# design.net
KiCad netlist of a schematic drawn in Altium Designer
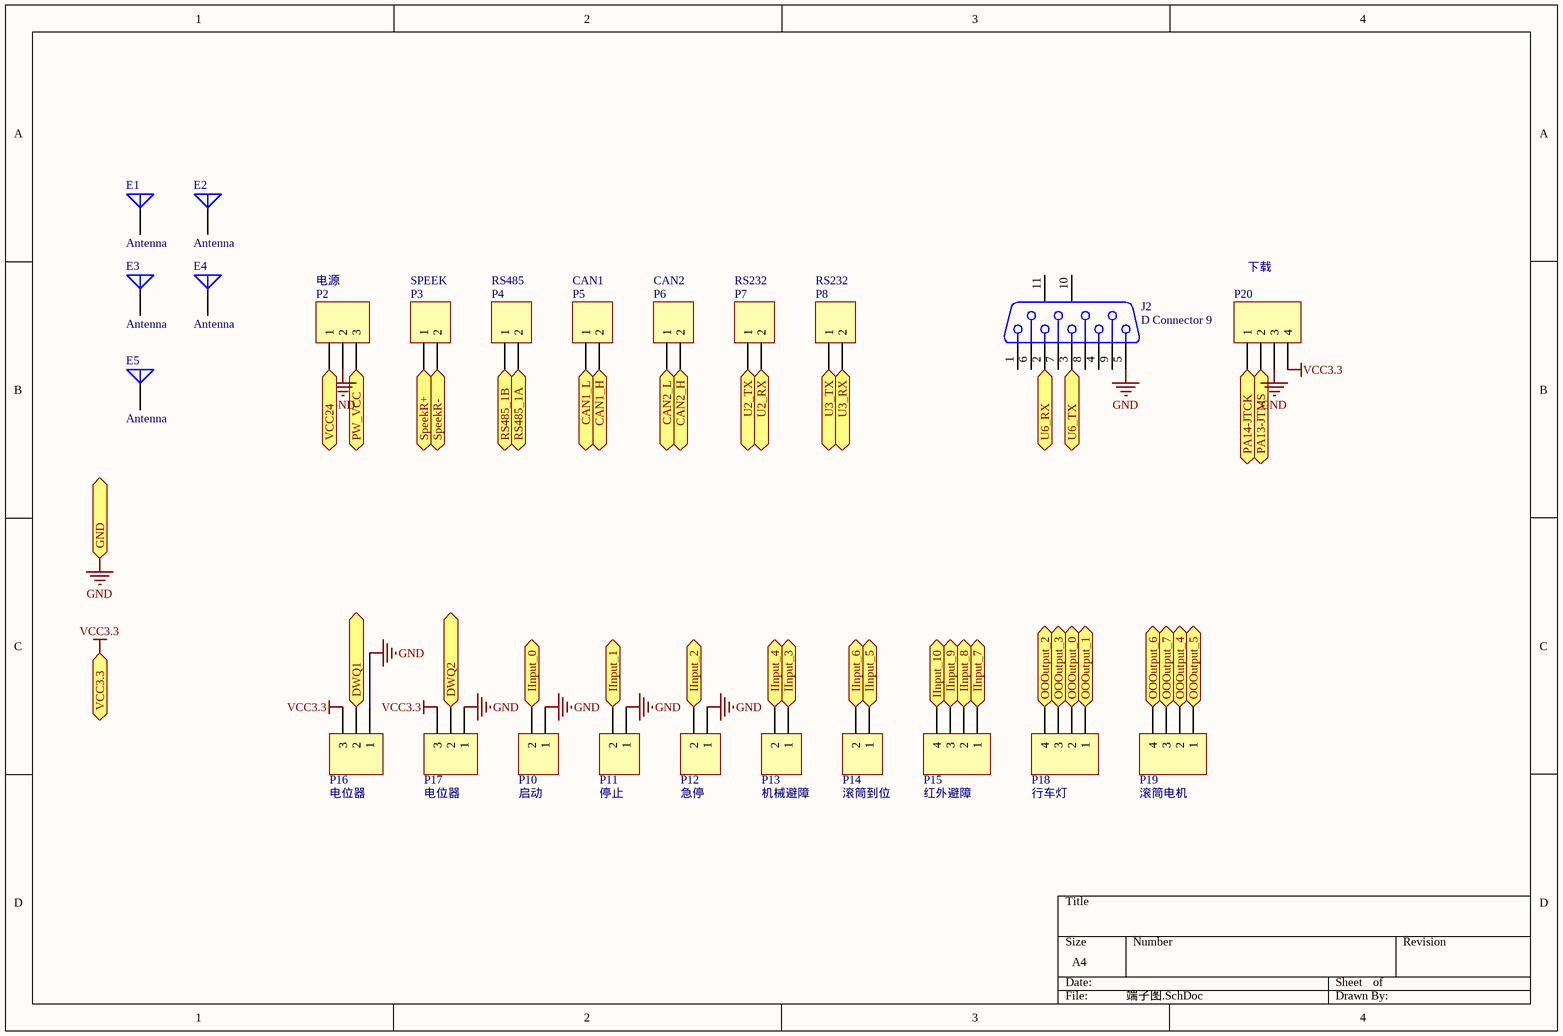
[diagram p0: 端子图.SchDoc]

(export (version "E")
  (design (tool "Eeschema 10.0.6"))
  (components
    (comp (ref "E1")
      (value "Antenna")
      (footprint "定位孔 Φ3.2")
      (description "Generic Antenna")
      (fields (field (name "PUBLISHER") "Altium Limited"))
      (libsource (lib "Miscellaneous Devices") (part "Antenna"))
    )
    (comp (ref "E2")
      (value "Antenna")
      (footprint "定位孔 Φ3.2")
      (description "Generic Antenna")
      (fields (field (name "PUBLISHER") "Altium Limited"))
      (libsource (lib "Miscellaneous Devices") (part "Antenna"))
    )
    (comp (ref "E3")
      (value "Antenna")
      (footprint "定位孔 Φ3.2")
      (description "Generic Antenna")
      (fields (field (name "PUBLISHER") "Altium Limited"))
      (libsource (lib "Miscellaneous Devices") (part "Antenna"))
    )
    (comp (ref "E4")
      (value "Antenna")
      (footprint "定位孔 Φ3.2")
      (description "Generic Antenna")
      (fields (field (name "PUBLISHER") "Altium Limited"))
      (libsource (lib "Miscellaneous Devices") (part "Antenna"))
    )
    (comp (ref "E5")
      (value "Antenna")
      (footprint "定位孔 Φ3.2")
      (description "Generic Antenna")
      (fields (field (name "PUBLISHER") "Altium Limited"))
      (libsource (lib "Miscellaneous Devices") (part "Antenna"))
    )
    (comp (ref "J2")
      (value "D Connector 9")
      (footprint "DSUB1.385-2H9")
      (description "Receptacle Assembly, 9 Position, Right Angle")
      (fields (field (name "PUBLISHER") "Altium Limited"))
      (libsource (lib "Miscellaneous Connectors") (part "D Connector 9"))
    )
    (comp (ref "P2")
      (value "电源")
      (footprint "DZ-3-5.08")
      (description "Header, 3-Pin")
      (fields (field (name "PUBLISHER") "Altium Limited"))
      (libsource (lib "") (part "Header 3_1"))
    )
    (comp (ref "P3")
      (value "SPEEK")
      (footprint "DZ-2-5.08")
      (description "Header, 2-Pin")
      (fields (field (name "PUBLISHER") "Altium Limited"))
      (libsource (lib "") (part "Header 2_1"))
    )
    (comp (ref "P4")
      (value "RS485")
      (footprint "DZ-2-5.08")
      (description "Header, 2-Pin")
      (fields (field (name "PUBLISHER") "Altium Limited"))
      (libsource (lib "") (part "Header 2_1"))
    )
    (comp (ref "P5")
      (value "CAN1")
      (footprint "DZ-2-5.08")
      (description "Header, 2-Pin")
      (fields (field (name "PUBLISHER") "Altium Limited"))
      (libsource (lib "") (part "Header 2_1"))
    )
    (comp (ref "P6")
      (value "CAN2")
      (footprint "DZ-2-5.08")
      (description "Header, 2-Pin")
      (fields (field (name "PUBLISHER") "Altium Limited"))
      (libsource (lib "") (part "Header 2_1"))
    )
    (comp (ref "P7")
      (value "RS232")
      (footprint "DZ-2-5.08")
      (description "Header, 2-Pin")
      (fields (field (name "PUBLISHER") "Altium Limited"))
      (libsource (lib "") (part "Header 2_1"))
    )
    (comp (ref "P8")
      (value "RS232")
      (footprint "DZ-2-5.08")
      (description "Header, 2-Pin")
      (fields (field (name "PUBLISHER") "Altium Limited"))
      (libsource (lib "") (part "Header 2_1"))
    )
    (comp (ref "P10")
      (value "启动")
      (footprint "DZ-2-5.08")
      (description "Header, 2-Pin")
      (fields (field (name "PUBLISHER") "Altium Limited"))
      (libsource (lib "Miscellaneous Connectors") (part "Header 2"))
    )
    (comp (ref "P11")
      (value "停止")
      (footprint "DZ-2-5.08")
      (description "Header, 2-Pin")
      (fields (field (name "PUBLISHER") "Altium Limited"))
      (libsource (lib "Miscellaneous Connectors") (part "Header 2"))
    )
    (comp (ref "P12")
      (value "急停")
      (footprint "DZ-2-5.08")
      (description "Header, 2-Pin")
      (fields (field (name "PUBLISHER") "Altium Limited"))
      (libsource (lib "Miscellaneous Connectors") (part "Header 2"))
    )
    (comp (ref "P13")
      (value "机械避障")
      (footprint "DZ-2-5.08")
      (description "Header, 2-Pin")
      (fields (field (name "PUBLISHER") "Altium Limited"))
      (libsource (lib "Miscellaneous Connectors") (part "Header 2"))
    )
    (comp (ref "P14")
      (value "滚筒到位")
      (footprint "DZ-2-5.08")
      (description "Header, 2-Pin")
      (fields (field (name "PUBLISHER") "Altium Limited"))
      (libsource (lib "Miscellaneous Connectors") (part "Header 2"))
    )
    (comp (ref "P15")
      (value "红外避障")
      (footprint "DZ-4-5.08")
      (description "Header, 4-Pin")
      (fields (field (name "PUBLISHER") "Altium Limited"))
      (libsource (lib "Miscellaneous Connectors") (part "Header 4"))
    )
    (comp (ref "P16")
      (value "电位器")
      (footprint "DZ-3-5.08")
      (description "Header, 3-Pin")
      (fields (field (name "PUBLISHER") "Altium Limited"))
      (libsource (lib "Miscellaneous Connectors") (part "Header 3"))
    )
    (comp (ref "P17")
      (value "电位器")
      (footprint "DZ-3-5.08")
      (description "Header, 3-Pin")
      (fields (field (name "PUBLISHER") "Altium Limited"))
      (libsource (lib "Miscellaneous Connectors") (part "Header 3"))
    )
    (comp (ref "P18")
      (value "行车灯")
      (footprint "DZ-4-5.08")
      (description "Header, 4-Pin")
      (fields (field (name "PUBLISHER") "Altium Limited"))
      (libsource (lib "Miscellaneous Connectors") (part "Header 4"))
    )
    (comp (ref "P19")
      (value "滚筒电机")
      (footprint "DZ-4-5.08")
      (description "Header, 4-Pin")
      (fields (field (name "PUBLISHER") "Altium Limited"))
      (libsource (lib "Miscellaneous Connectors") (part "Header 4"))
    )
    (comp (ref "P20")
      (value "下载")
      (footprint "DZ-4-5.08")
      (description "Header, 4-Pin")
      (fields (field (name "PUBLISHER") "Altium Limited"))
      (libsource (lib "") (part "Header 4_1"))
    )
  )
  (nets
    (net (code "1") (name "/CAN1_H") (class "Default")
      (node (ref "P5") (pin "2") (pinfunction "2_2") (pintype "passive"))
    )
    (net (code "2") (name "/CAN1_L") (class "Default")
      (node (ref "P5") (pin "1") (pinfunction "1_1") (pintype "passive"))
    )
    (net (code "3") (name "/CAN2_H") (class "Default")
      (node (ref "P6") (pin "2") (pinfunction "2_2") (pintype "passive"))
    )
    (net (code "4") (name "/CAN2_L") (class "Default")
      (node (ref "P6") (pin "1") (pinfunction "1_1") (pintype "passive"))
    )
    (net (code "5") (name "/DWQ1") (class "Default")
      (node (ref "P16") (pin "2") (pinfunction "2_2") (pintype "passive"))
    )
    (net (code "6") (name "/DWQ2") (class "Default")
      (node (ref "P17") (pin "2") (pinfunction "2_2") (pintype "passive"))
    )
    (net (code "7") (name "/IInput_0") (class "Default")
      (node (ref "P10") (pin "2") (pinfunction "2_2") (pintype "passive"))
    )
    (net (code "8") (name "/IInput_1") (class "Default")
      (node (ref "P11") (pin "2") (pinfunction "2_2") (pintype "passive"))
    )
    (net (code "9") (name "/IInput_2") (class "Default")
      (node (ref "P12") (pin "2") (pinfunction "2_2") (pintype "passive"))
    )
    (net (code "10") (name "/IInput_3") (class "Default")
      (node (ref "P13") (pin "1") (pinfunction "1_1") (pintype "passive"))
    )
    (net (code "11") (name "/IInput_4") (class "Default")
      (node (ref "P13") (pin "2") (pinfunction "2_2") (pintype "passive"))
    )
    (net (code "12") (name "/IInput_5") (class "Default")
      (node (ref "P14") (pin "1") (pinfunction "1_1") (pintype "passive"))
    )
    (net (code "13") (name "/IInput_6") (class "Default")
      (node (ref "P14") (pin "2") (pinfunction "2_2") (pintype "passive"))
    )
    (net (code "14") (name "/IInput_7") (class "Default")
      (node (ref "P15") (pin "1") (pinfunction "1_1") (pintype "passive"))
    )
    (net (code "15") (name "/IInput_8") (class "Default")
      (node (ref "P15") (pin "2") (pinfunction "2_2") (pintype "passive"))
    )
    (net (code "16") (name "/IInput_9") (class "Default")
      (node (ref "P15") (pin "3") (pinfunction "3_3") (pintype "passive"))
    )
    (net (code "17") (name "/IInput_10") (class "Default")
      (node (ref "P15") (pin "4") (pinfunction "4_4") (pintype "passive"))
    )
    (net (code "18") (name "/OOOutput_0") (class "Default")
      (node (ref "P18") (pin "2") (pinfunction "2_2") (pintype "passive"))
    )
    (net (code "19") (name "/OOOutput_1") (class "Default")
      (node (ref "P18") (pin "1") (pinfunction "1_1") (pintype "passive"))
    )
    (net (code "20") (name "/OOOutput_2") (class "Default")
      (node (ref "P18") (pin "4") (pinfunction "4_4") (pintype "passive"))
    )
    (net (code "21") (name "/OOOutput_3") (class "Default")
      (node (ref "P18") (pin "3") (pinfunction "3_3") (pintype "passive"))
    )
    (net (code "22") (name "/OOOutput_4") (class "Default")
      (node (ref "P19") (pin "2") (pinfunction "2_2") (pintype "passive"))
    )
    (net (code "23") (name "/OOOutput_5") (class "Default")
      (node (ref "P19") (pin "1") (pinfunction "1_1") (pintype "passive"))
    )
    (net (code "24") (name "/OOOutput_6") (class "Default")
      (node (ref "P19") (pin "4") (pinfunction "4_4") (pintype "passive"))
    )
    (net (code "25") (name "/OOOutput_7") (class "Default")
      (node (ref "P19") (pin "3") (pinfunction "3_3") (pintype "passive"))
    )
    (net (code "26") (name "/PA13-JTMS") (class "Default")
      (node (ref "P20") (pin "2") (pinfunction "2_2") (pintype "passive"))
    )
    (net (code "27") (name "/PA14-JTCK") (class "Default")
      (node (ref "P20") (pin "1") (pinfunction "1_1") (pintype "passive"))
    )
    (net (code "28") (name "/PW_VCC") (class "Default")
      (node (ref "P2") (pin "3") (pinfunction "3_3") (pintype "passive"))
    )
    (net (code "29") (name "/RS485_1A") (class "Default")
      (node (ref "P4") (pin "2") (pinfunction "2_2") (pintype "passive"))
    )
    (net (code "30") (name "/RS485_1B") (class "Default")
      (node (ref "P4") (pin "1") (pinfunction "1_1") (pintype "passive"))
    )
    (net (code "31") (name "/SpeekR+") (class "Default")
      (node (ref "P3") (pin "1") (pinfunction "1_1") (pintype "passive"))
    )
    (net (code "32") (name "/SpeekR-") (class "Default")
      (node (ref "P3") (pin "2") (pinfunction "2_2") (pintype "passive"))
    )
    (net (code "33") (name "/U2_RX") (class "Default")
      (node (ref "P7") (pin "2") (pinfunction "2_2") (pintype "passive"))
    )
    (net (code "34") (name "/U2_TX") (class "Default")
      (node (ref "P7") (pin "1") (pinfunction "1_1") (pintype "passive"))
    )
    (net (code "35") (name "/U3_RX") (class "Default")
      (node (ref "P8") (pin "2") (pinfunction "2_2") (pintype "passive"))
    )
    (net (code "36") (name "/U3_TX") (class "Default")
      (node (ref "P8") (pin "1") (pinfunction "1_1") (pintype "passive"))
    )
    (net (code "37") (name "/U6_RX") (class "Default")
      (node (ref "J2") (pin "2") (pinfunction "2_2") (pintype "passive"))
    )
    (net (code "38") (name "/U6_TX") (class "Default")
      (node (ref "J2") (pin "3") (pinfunction "3_3") (pintype "passive"))
    )
    (net (code "39") (name "/VCC24") (class "Default")
      (node (ref "P2") (pin "1") (pinfunction "1_1") (pintype "passive"))
    )
    (net (code "40") (name "GND") (class "Default")
      (node (ref "J2") (pin "5") (pinfunction "5_5") (pintype "passive"))
      (node (ref "P10") (pin "1") (pinfunction "1_1") (pintype "passive"))
      (node (ref "P11") (pin "1") (pinfunction "1_1") (pintype "passive"))
      (node (ref "P12") (pin "1") (pinfunction "1_1") (pintype "passive"))
      (node (ref "P16") (pin "1") (pinfunction "1_1") (pintype "passive"))
      (node (ref "P17") (pin "1") (pinfunction "1_1") (pintype "passive"))
      (node (ref "P2") (pin "2") (pinfunction "2_2") (pintype "passive"))
      (node (ref "P20") (pin "3") (pinfunction "3_3") (pintype "passive"))
    )
    (net (code "41") (name "VCC3.3") (class "Default")
      (node (ref "P16") (pin "3") (pinfunction "3_3") (pintype "passive"))
      (node (ref "P17") (pin "3") (pinfunction "3_3") (pintype "passive"))
      (node (ref "P20") (pin "4") (pinfunction "4_4") (pintype "passive"))
    )
    (net (code "42") (name "unconnected-(E1-A-Pad1)") (class "Default")
      (node (ref "E1") (pin "1") (pinfunction "A_1") (pintype "passive"))
    )
    (net (code "43") (name "unconnected-(E2-A-Pad1)") (class "Default")
      (node (ref "E2") (pin "1") (pinfunction "A_1") (pintype "passive"))
    )
    (net (code "44") (name "unconnected-(E3-A-Pad1)") (class "Default")
      (node (ref "E3") (pin "1") (pinfunction "A_1") (pintype "passive"))
    )
    (net (code "45") (name "unconnected-(E4-A-Pad1)") (class "Default")
      (node (ref "E4") (pin "1") (pinfunction "A_1") (pintype "passive"))
    )
    (net (code "46") (name "unconnected-(E5-A-Pad1)") (class "Default")
      (node (ref "E5") (pin "1") (pinfunction "A_1") (pintype "passive"))
    )
    (net (code "47") (name "unconnected-(J2-MH1-Pad10)") (class "Default")
      (node (ref "J2") (pin "10") (pinfunction "MH1_10") (pintype "passive"))
    )
    (net (code "48") (name "unconnected-(J2-MH2-Pad11)") (class "Default")
      (node (ref "J2") (pin "11") (pinfunction "MH2_11") (pintype "passive"))
    )
    (net (code "49") (name "unconnected-(J2-Pad1)") (class "Default")
      (node (ref "J2") (pin "1") (pinfunction "1_1") (pintype "passive"))
    )
    (net (code "50") (name "unconnected-(J2-Pad4)") (class "Default")
      (node (ref "J2") (pin "4") (pinfunction "4_4") (pintype "passive"))
    )
    (net (code "51") (name "unconnected-(J2-Pad6)") (class "Default")
      (node (ref "J2") (pin "6") (pinfunction "6_6") (pintype "passive"))
    )
    (net (code "52") (name "unconnected-(J2-Pad7)") (class "Default")
      (node (ref "J2") (pin "7") (pinfunction "7_7") (pintype "passive"))
    )
    (net (code "53") (name "unconnected-(J2-Pad8)") (class "Default")
      (node (ref "J2") (pin "8") (pinfunction "8_8") (pintype "passive"))
    )
    (net (code "54") (name "unconnected-(J2-Pad9)") (class "Default")
      (node (ref "J2") (pin "9") (pinfunction "9_9") (pintype "passive"))
    )
  )
)
